# Sheet1.net
KiCad netlist of a schematic drawn in Altium Designer
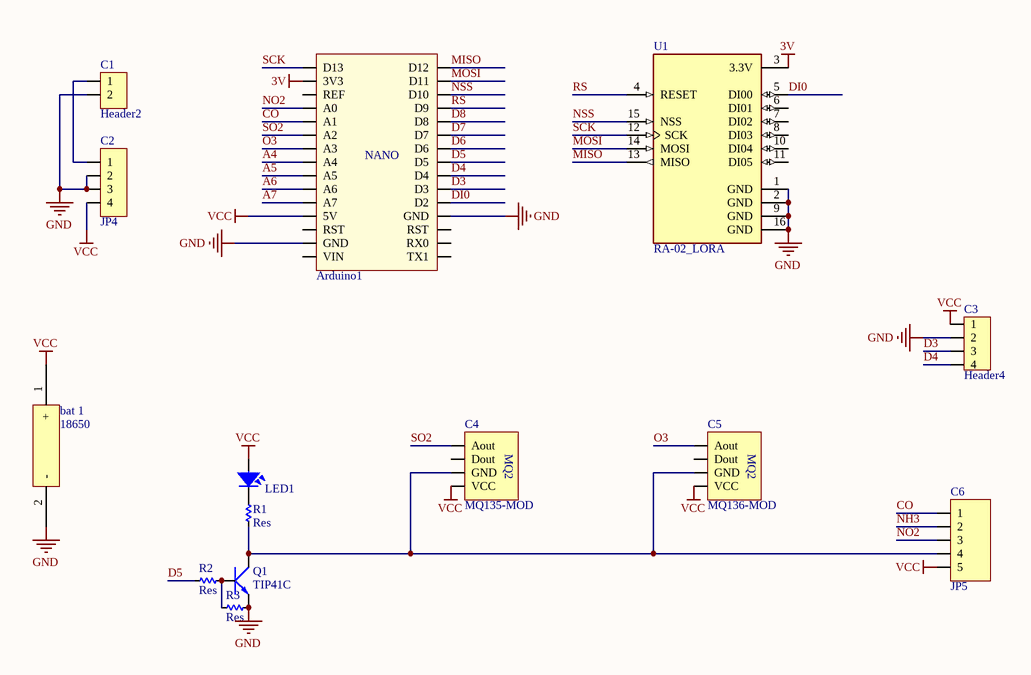
[diagram p0: Sheet1.SchDoc]

(export (version "E")
  (design (tool "Eeschema 10.0.6"))
  (components
    (comp (ref "Arduino1")
      (value "Arduino Nano")
      (footprint "Arduino Nano")
      (description "Arduino NANO")
      (libsource (lib "LIBRARY") (part "Arduino Nano"))
    )
    (comp (ref "bat 1") (value "18650") (footprint "18650") (libsource (lib "18650") (part "18650")))
    (comp (ref "C1")
      (value "Header2")
      (footprint "HDR2")
      (description "Header IDC, 2 x 1 Pin Vertical 2.54mm Pitch (Non-Boxed, Male)")
      (fields
        (field (name "MANUFACTURER") "Würth Elektronik eiSos GmbH")
        (field (name "PARTNO") "613002143121")
        (field (name "CREATED BY") "Karrer Zheng")
      )
      (libsource (lib "LIBRARY") (part "Header2"))
    )
    (comp (ref "C2")
      (value "JP4")
      (footprint "JP4-C1T")
      (description "WR-PHD 2.54 mm Angled Socket Header")
      (fields
        (field (name "MANUFACTURER") "Würth Elektronik eiSos GmbH")
        (field (name "PARTNO") "613004143121")
        (field (name "CREATED BY") "Karrer Zheng")
      )
      (libsource (lib "LIBRARY") (part "JP4"))
    )
    (comp (ref "C3")
      (value "Header4")
      (footprint "HDR4")
      (description "Header IDC, 4 x 1 Pin Vertical 2.54mm Pitch (Non-Boxed, Male)")
      (fields
        (field (name "MANUFACTURER") "Würth Elektronik eiSos GmbH")
        (field (name "PARTNO") "613002143121")
        (field (name "CREATED BY") "Karrer Zheng")
      )
      (libsource (lib "LIBRARY") (part "Header4"))
    )
    (comp (ref "C4")
      (value "MQ135-MOD")
      (footprint "MQ2-MODULE")
      (fields
        (field (name "MANUFACTURER") "Würth Elektronik eiSos GmbH")
        (field (name "PARTNO") "613004143121")
        (field (name "CREATED BY") "Karrer Zheng")
      )
      (libsource (lib "LIBRARY") (part "MQ2-MOD"))
    )
    (comp (ref "C5")
      (value "MQ136-MOD")
      (footprint "MQ2-MODULE")
      (fields
        (field (name "MANUFACTURER") "Würth Elektronik eiSos GmbH")
        (field (name "PARTNO") "613004143121")
        (field (name "CREATED BY") "Karrer Zheng")
      )
      (libsource (lib "LIBRARY") (part "MQ2-MOD"))
    )
    (comp (ref "C6")
      (value "JP5")
      (footprint "JP5-C1T")
      (description "WR-PHD 2.54 mm Angled Socket Header")
      (fields
        (field (name "MANUFACTURER") "Würth Elektronik eiSos GmbH")
        (field (name "PARTNO") "613005143121")
        (field (name "CREATED BY") "Karrer Zheng")
      )
      (libsource (lib "LIBRARY") (part "JP5"))
    )
    (comp (ref "LED1")
      (value "LED")
      (footprint "LED-5-BLUE")
      (description "LED Single colour Green and Red")
      (libsource (lib "LIBRARY") (part "LED"))
    )
    (comp (ref "Q1")
      (value "TIP41C")
      (footprint "TO220-123")
      (description "NPN 2W, BCE")
      (libsource (lib "LIBRARY") (part "TIP41C"))
    )
    (comp (ref "R1")
      (value "Res")
      (footprint "RES-1/8WD")
      (fields
        (field (name "MANUFACTURER") "Generic Components")
        (field (name "PUBLISHER") "Altium Hobart Technology Centre")
      )
      (libsource (lib "LIBRARY") (part "Res"))
    )
    (comp (ref "R2")
      (value "Res")
      (footprint "RES-1/8WD")
      (fields
        (field (name "MANUFACTURER") "Generic Components")
        (field (name "PUBLISHER") "Altium Hobart Technology Centre")
      )
      (libsource (lib "LIBRARY") (part "Res"))
    )
    (comp (ref "R3")
      (value "Res")
      (footprint "RES-1/8WD")
      (fields
        (field (name "MANUFACTURER") "Generic Components")
        (field (name "PUBLISHER") "Altium Hobart Technology Centre")
      )
      (libsource (lib "LIBRARY") (part "Res"))
    )
    (comp (ref "U1")
      (value "RA-02_LORA")
      (footprint "MODULE_RA-02_LORA")
      (description "Ra-02 LoRa RF M5Stack Platform Evaluation Expansion Board")
      (fields (field (name "MP") "Ra-02 LoRa") (field (name "MF") "AI-Thinker"))
      (libsource (lib "RA-02_LORA") (part "RA-02_LORA"))
    )
  )
  (nets
    (net (code "1") (name "/A4") (class "Default")
      (node (ref "Arduino1") (pin "A4") (pinfunction "A4_A4") (pintype "passive"))
    )
    (net (code "2") (name "/A5") (class "Default")
      (node (ref "Arduino1") (pin "A5") (pinfunction "A5_A5") (pintype "passive"))
    )
    (net (code "3") (name "/A6") (class "Default")
      (node (ref "Arduino1") (pin "A6") (pinfunction "A6_A6") (pintype "passive"))
    )
    (net (code "4") (name "/A7") (class "Default")
      (node (ref "Arduino1") (pin "A7") (pinfunction "A7_A7") (pintype "passive"))
    )
    (net (code "5") (name "/CO") (class "Default")
      (node (ref "Arduino1") (pin "A1") (pinfunction "A1_A1") (pintype "passive"))
      (node (ref "C6") (pin "1") (pinfunction "1_1") (pintype "passive"))
    )
    (net (code "6") (name "/D3") (class "Default")
      (node (ref "Arduino1") (pin "D3") (pinfunction "D3_D3") (pintype "passive"))
      (node (ref "C3") (pin "3") (pinfunction "3_3") (pintype "passive"))
    )
    (net (code "7") (name "/D4") (class "Default")
      (node (ref "Arduino1") (pin "D4") (pinfunction "D4_D4") (pintype "passive"))
      (node (ref "C3") (pin "4") (pinfunction "4_4") (pintype "passive"))
    )
    (net (code "8") (name "/D5") (class "Default")
      (node (ref "Arduino1") (pin "D5") (pinfunction "D5_D5") (pintype "passive"))
      (node (ref "R2") (pin "2") (pinfunction "2_2") (pintype "passive"))
    )
    (net (code "9") (name "/D6") (class "Default")
      (node (ref "Arduino1") (pin "D6") (pinfunction "D6_D6") (pintype "passive"))
    )
    (net (code "10") (name "/D7") (class "Default")
      (node (ref "Arduino1") (pin "D7") (pinfunction "D7_D7") (pintype "passive"))
    )
    (net (code "11") (name "/D8") (class "Default")
      (node (ref "Arduino1") (pin "D8") (pinfunction "D8_D8") (pintype "passive"))
    )
    (net (code "12") (name "/DI0") (class "Default")
      (node (ref "Arduino1") (pin "D2") (pinfunction "D2_D2") (pintype "passive"))
      (node (ref "U1") (pin "5") (pinfunction "DI00_5") (pintype "bidirectional"))
    )
    (net (code "13") (name "/MISO") (class "Default")
      (node (ref "Arduino1") (pin "D12") (pinfunction "D12_D12") (pintype "passive"))
      (node (ref "U1") (pin "13") (pinfunction "MISO_13") (pintype "output"))
    )
    (net (code "14") (name "/MOSI") (class "Default")
      (node (ref "Arduino1") (pin "D11") (pinfunction "D11_D11") (pintype "passive"))
      (node (ref "U1") (pin "14") (pinfunction "MOSI_14") (pintype "input"))
    )
    (net (code "15") (name "/NH3") (class "Default")
      (node (ref "C6") (pin "2") (pinfunction "2_2") (pintype "passive"))
    )
    (net (code "16") (name "/NO2") (class "Default")
      (node (ref "Arduino1") (pin "A0") (pinfunction "A0_A0") (pintype "passive"))
      (node (ref "C6") (pin "3") (pinfunction "3_3") (pintype "passive"))
    )
    (net (code "17") (name "/NSS") (class "Default")
      (node (ref "Arduino1") (pin "D10") (pinfunction "D10_D10") (pintype "passive"))
      (node (ref "U1") (pin "15") (pinfunction "NSS_15") (pintype "input"))
    )
    (net (code "18") (name "/O3") (class "Default")
      (node (ref "Arduino1") (pin "A3") (pinfunction "A3_A3") (pintype "passive"))
      (node (ref "C5") (pin "1") (pinfunction "Aout_1") (pintype "passive"))
    )
    (net (code "19") (name "/RS") (class "Default")
      (node (ref "Arduino1") (pin "D9") (pinfunction "D9_D9") (pintype "passive"))
      (node (ref "U1") (pin "4") (pinfunction "RESET_4") (pintype "input"))
    )
    (net (code "20") (name "/SCK") (class "Default")
      (node (ref "Arduino1") (pin "D13") (pinfunction "D13_D13") (pintype "passive"))
      (node (ref "U1") (pin "12") (pinfunction "SCK_12") (pintype "input"))
    )
    (net (code "21") (name "/SO2") (class "Default")
      (node (ref "Arduino1") (pin "A2") (pinfunction "A2_A2") (pintype "passive"))
      (node (ref "C4") (pin "1") (pinfunction "Aout_1") (pintype "passive"))
    )
    (net (code "22") (name "3V") (class "Default")
      (node (ref "Arduino1") (pin "3V3") (pinfunction "3V3_3V3") (pintype "passive"))
      (node (ref "U1") (pin "3") (pinfunction "3.3V_3") (pintype "power_in"))
    )
    (net (code "23") (name "GND") (class "Default")
      (node (ref "Arduino1") (pin "GND") (pinfunction "GND_GND") (pintype "passive"))
      (node (ref "C1") (pin "2") (pinfunction "2_2") (pintype "passive"))
      (node (ref "C2") (pin "2") (pinfunction "2_2") (pintype "passive"))
      (node (ref "C2") (pin "3") (pinfunction "3_3") (pintype "passive"))
      (node (ref "C3") (pin "2") (pinfunction "2_2") (pintype "passive"))
      (node (ref "Q1") (pin "3") (pinfunction "E_3") (pintype "passive"))
      (node (ref "R3") (pin "1") (pinfunction "1_1") (pintype "passive"))
      (node (ref "U1") (pin "1") (pinfunction "GND_1") (pintype "power_in"))
      (node (ref "U1") (pin "16") (pinfunction "GND_16") (pintype "power_in"))
      (node (ref "U1") (pin "2") (pinfunction "GND_2") (pintype "power_in"))
      (node (ref "U1") (pin "9") (pinfunction "GND_9") (pintype "power_in"))
      (node (ref "bat 1") (pin "2") (pinfunction "-_2") (pintype "passive"))
    )
    (net (code "24") (name "Net-(C1-Pad1)") (class "Default")
      (node (ref "C1") (pin "1") (pinfunction "1_1") (pintype "passive"))
      (node (ref "C2") (pin "1") (pinfunction "1_1") (pintype "passive"))
    )
    (net (code "25") (name "Net-(C4-GND)") (class "Default")
      (node (ref "C4") (pin "3") (pinfunction "GND_3") (pintype "passive"))
      (node (ref "C5") (pin "3") (pinfunction "GND_3") (pintype "passive"))
      (node (ref "C6") (pin "4") (pinfunction "4_4") (pintype "passive"))
      (node (ref "Q1") (pin "2") (pinfunction "C_2") (pintype "passive"))
      (node (ref "R1") (pin "2") (pinfunction "2_2") (pintype "passive"))
    )
    (net (code "26") (name "Net-(LED1-Pad2)") (class "Default")
      (node (ref "LED1") (pin "2") (pinfunction "2_2") (pintype "passive"))
      (node (ref "R1") (pin "1") (pinfunction "1_1") (pintype "passive"))
    )
    (net (code "27") (name "Net-(Q1-B)") (class "Default")
      (node (ref "Q1") (pin "1") (pinfunction "B_1") (pintype "passive"))
      (node (ref "R2") (pin "1") (pinfunction "1_1") (pintype "passive"))
      (node (ref "R3") (pin "2") (pinfunction "2_2") (pintype "passive"))
    )
    (net (code "28") (name "VCC") (class "Default")
      (node (ref "Arduino1") (pin "5V") (pinfunction "5V_5V") (pintype "passive"))
      (node (ref "C2") (pin "4") (pinfunction "4_4") (pintype "passive"))
      (node (ref "C3") (pin "1") (pinfunction "1_1") (pintype "passive"))
      (node (ref "C4") (pin "4") (pinfunction "VCC_4") (pintype "passive"))
      (node (ref "C5") (pin "4") (pinfunction "VCC_4") (pintype "passive"))
      (node (ref "C6") (pin "5") (pinfunction "5_5") (pintype "passive"))
      (node (ref "LED1") (pin "1") (pinfunction "1_1") (pintype "passive"))
      (node (ref "bat 1") (pin "1") (pinfunction "+_1") (pintype "passive"))
    )
    (net (code "29") (name "unconnected-(Arduino1-PadREF)") (class "Default")
      (node (ref "Arduino1") (pin "REF") (pinfunction "REF_REF") (pintype "passive"))
    )
    (net (code "30") (name "unconnected-(Arduino1-PadRST)") (class "Default")
      (node (ref "Arduino1") (pin "RST") (pinfunction "RST_RST") (pintype "passive"))
    )
    (net (code "31") (name "unconnected-(Arduino1-PadRST)_1") (class "Default")
      (node (ref "Arduino1") (pin "RST") (pinfunction "RST_RST") (pintype "passive"))
    )
    (net (code "32") (name "unconnected-(Arduino1-PadRX0)") (class "Default")
      (node (ref "Arduino1") (pin "RX0") (pinfunction "RX0_RX0") (pintype "passive"))
    )
    (net (code "33") (name "unconnected-(Arduino1-PadTX1)") (class "Default")
      (node (ref "Arduino1") (pin "TX1") (pinfunction "TX1_TX1") (pintype "passive"))
    )
    (net (code "34") (name "unconnected-(Arduino1-PadVIN)") (class "Default")
      (node (ref "Arduino1") (pin "VIN") (pinfunction "VIN_VIN") (pintype "passive"))
    )
    (net (code "35") (name "unconnected-(C4-Dout-Pad2)") (class "Default")
      (node (ref "C4") (pin "2") (pinfunction "Dout_2") (pintype "passive"))
    )
    (net (code "36") (name "unconnected-(C5-Dout-Pad2)") (class "Default")
      (node (ref "C5") (pin "2") (pinfunction "Dout_2") (pintype "passive"))
    )
    (net (code "37") (name "unconnected-(U1-DI01-Pad6)") (class "Default")
      (node (ref "U1") (pin "6") (pinfunction "DI01_6") (pintype "bidirectional"))
    )
    (net (code "38") (name "unconnected-(U1-DI02-Pad7)") (class "Default")
      (node (ref "U1") (pin "7") (pinfunction "DI02_7") (pintype "bidirectional"))
    )
    (net (code "39") (name "unconnected-(U1-DI03-Pad8)") (class "Default")
      (node (ref "U1") (pin "8") (pinfunction "DI03_8") (pintype "bidirectional"))
    )
    (net (code "40") (name "unconnected-(U1-DI04-Pad10)") (class "Default")
      (node (ref "U1") (pin "10") (pinfunction "DI04_10") (pintype "bidirectional"))
    )
    (net (code "41") (name "unconnected-(U1-DI05-Pad11)") (class "Default")
      (node (ref "U1") (pin "11") (pinfunction "DI05_11") (pintype "bidirectional"))
    )
  )
)
